# MCP960XL-L0X-RL0X_EVM_v1_teardrops.net
KiCad netlist of a schematic drawn in EAGLE
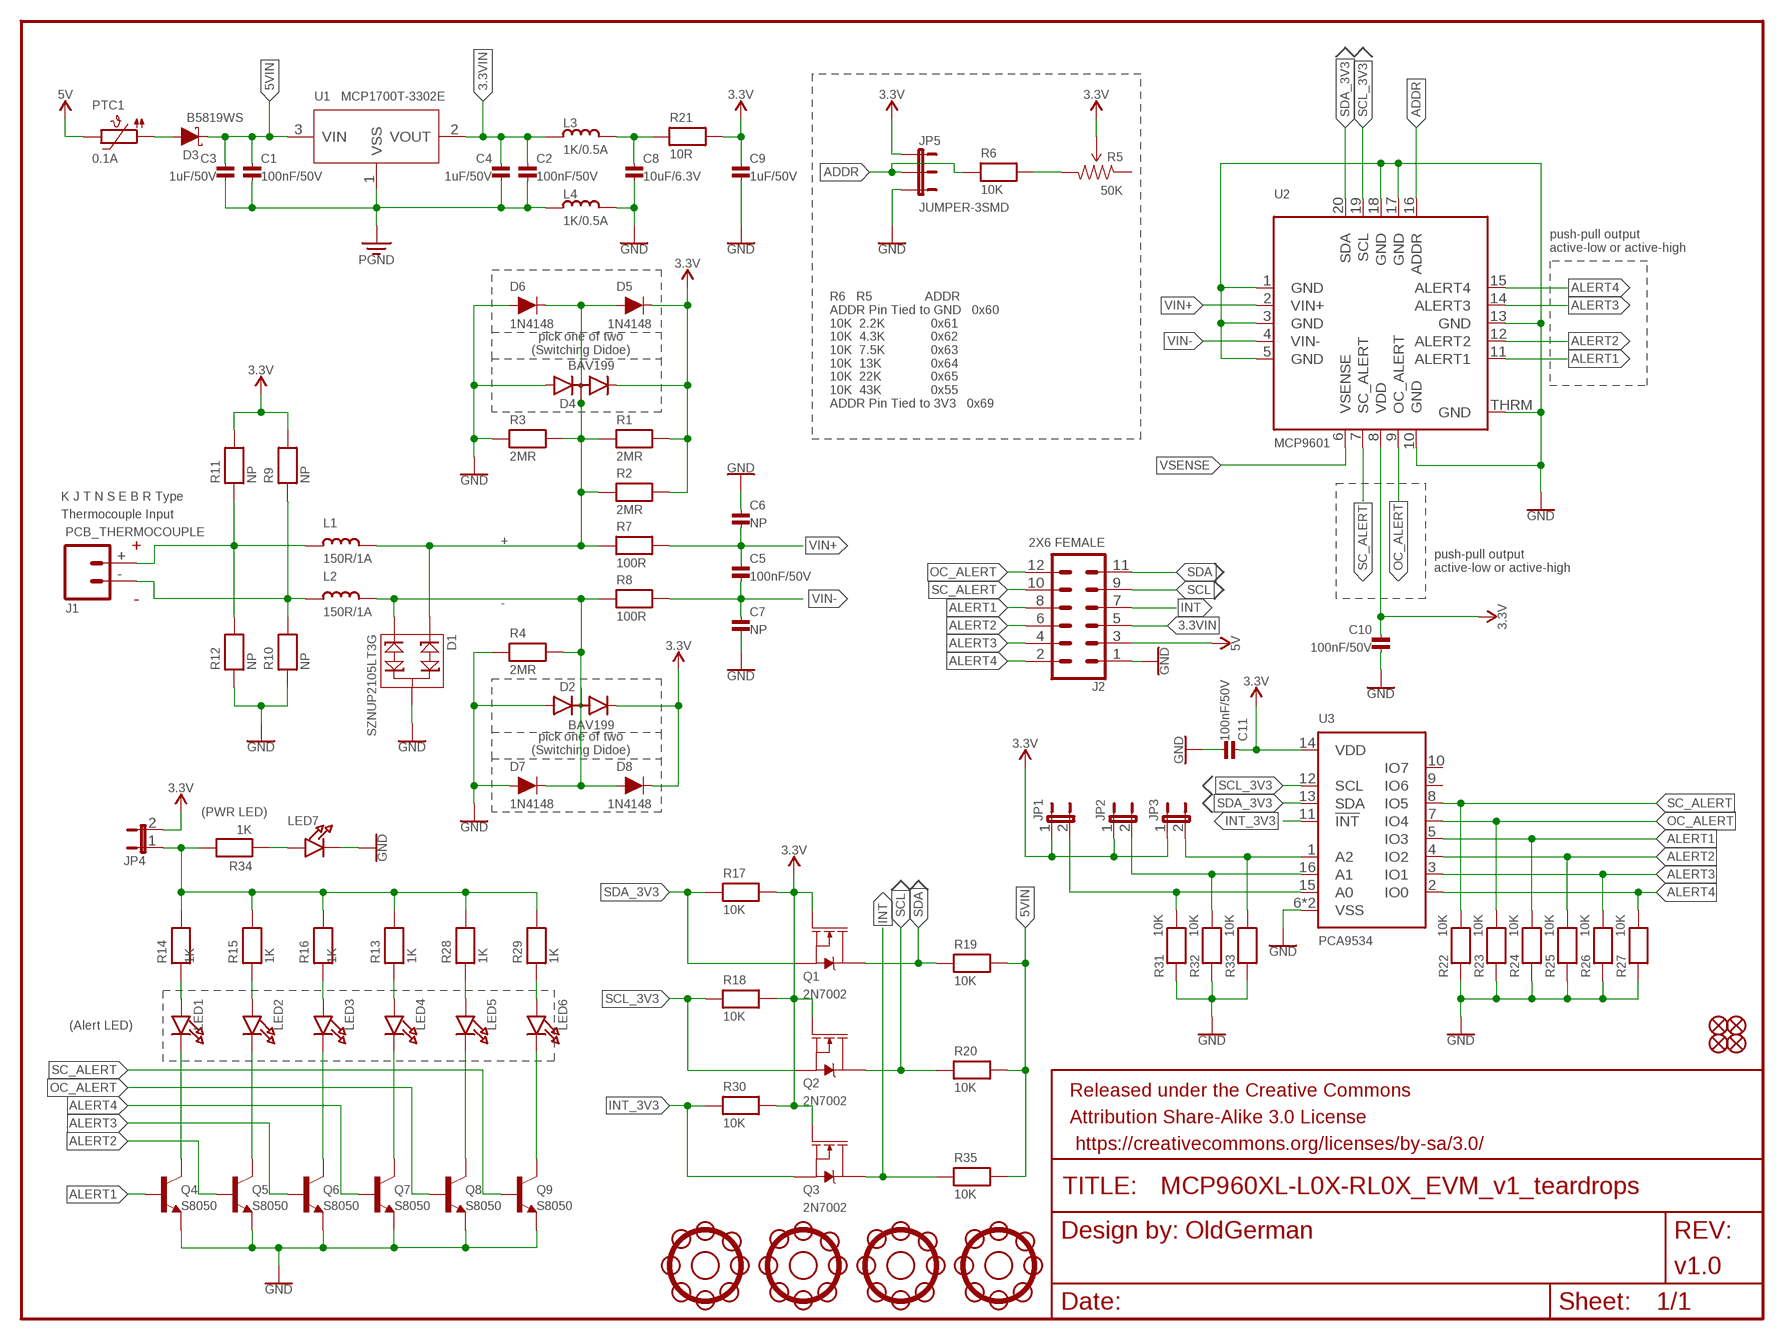
[diagram p0: schematic, sheet 1]

(export (version "E")
  (design (tool "Eeschema 10.0.6"))
  (components
    (comp (ref "C1")
      (value "100nF/50V")
      (footprint "eagle-import:0603")
      (libsource (lib "eagle-import") (part "CAP_CERAMIC0603"))
    )
    (comp (ref "C2")
      (value "100nF/50V")
      (footprint "eagle-import:0603")
      (libsource (lib "eagle-import") (part "CAP_CERAMIC0603"))
    )
    (comp (ref "C3")
      (value "1uF/50V")
      (footprint "eagle-import:0603")
      (libsource (lib "eagle-import") (part "CAP_CERAMIC0603"))
    )
    (comp (ref "C4")
      (value "1uF/50V")
      (footprint "eagle-import:0603")
      (libsource (lib "eagle-import") (part "CAP_CERAMIC0603"))
    )
    (comp (ref "C5")
      (value "100nF/50V")
      (footprint "eagle-import:0603")
      (libsource (lib "eagle-import") (part "CAP_CERAMIC0603"))
    )
    (comp (ref "C6")
      (value "NP")
      (footprint "eagle-import:0603")
      (libsource (lib "eagle-import") (part "CAP_CERAMIC0603"))
    )
    (comp (ref "C7")
      (value "NP")
      (footprint "eagle-import:0603")
      (libsource (lib "eagle-import") (part "CAP_CERAMIC0603"))
    )
    (comp (ref "C8")
      (value "10uF/6.3V")
      (footprint "eagle-import:0603")
      (libsource (lib "eagle-import") (part "CAP_CERAMIC0603"))
    )
    (comp (ref "C9")
      (value "1uF/50V")
      (footprint "eagle-import:0603")
      (libsource (lib "eagle-import") (part "CAP_CERAMIC0603"))
    )
    (comp (ref "C10")
      (value "100nF/50V")
      (footprint "eagle-import:0603")
      (libsource (lib "eagle-import") (part "CAP_CERAMIC0603"))
    )
    (comp (ref "C11")
      (value "100nF/50V")
      (footprint "eagle-import:0603")
      (libsource (lib "eagle-import") (part "CAP_CERAMIC0603"))
    )
    (comp (ref "D1")
      (value "SZNUP2105LT3G")
      (footprint "eagle-import:SOT23-3")
      (libsource (lib "eagle-import") (part "SZNUP2105LT3G"))
    )
    (comp (ref "D2")
      (value "BAV199")
      (footprint "eagle-import:SOT23-3")
      (libsource (lib "eagle-import") (part "BAV199"))
    )
    (comp (ref "D3")
      (value "B5819WS")
      (footprint "eagle-import:SOD-323")
      (libsource (lib "eagle-import") (part "DIODE_SCHOTTKYSOD323"))
    )
    (comp (ref "D4")
      (value "BAV199")
      (footprint "eagle-import:SOT23-3")
      (libsource (lib "eagle-import") (part "BAV199"))
    )
    (comp (ref "D5")
      (value "1N4148")
      (footprint "eagle-import:SOD-323")
      (libsource (lib "eagle-import") (part "DIODE"))
    )
    (comp (ref "D6")
      (value "1N4148")
      (footprint "eagle-import:SOD-323")
      (libsource (lib "eagle-import") (part "DIODE"))
    )
    (comp (ref "D7")
      (value "1N4148")
      (footprint "eagle-import:SOD-323")
      (libsource (lib "eagle-import") (part "DIODE"))
    )
    (comp (ref "D8")
      (value "1N4148")
      (footprint "eagle-import:SOD-323")
      (libsource (lib "eagle-import") (part "DIODE"))
    )
    (comp (ref "FID1")
      (value "FIDUCIAL1X2.5")
      (footprint "eagle-import:FIDUCIAL-1X2.5")
      (libsource (lib "eagle-import") (part "FIDUCIAL1X2.5"))
    )
    (comp (ref "FID2")
      (value "FIDUCIAL1X2.5")
      (footprint "eagle-import:FIDUCIAL-1X2.5")
      (libsource (lib "eagle-import") (part "FIDUCIAL1X2.5"))
    )
    (comp (ref "FID3")
      (value "FIDUCIAL1X2.5")
      (footprint "eagle-import:FIDUCIAL-1X2.5")
      (libsource (lib "eagle-import") (part "FIDUCIAL1X2.5"))
    )
    (comp (ref "FID4")
      (value "FIDUCIAL1X2.5")
      (footprint "eagle-import:FIDUCIAL-1X2.5")
      (libsource (lib "eagle-import") (part "FIDUCIAL1X2.5"))
    )
    (comp (ref "FRAME1")
      (value "FRAME-LETTER")
      (footprint "eagle-import:CREATIVE_COMMONS")
      (libsource (lib "eagle-import") (part "FRAME-LETTER"))
    )
    (comp (ref "J1")
      (value "PCB_THERMOCOUPLE")
      (footprint "eagle-import:PCC-SMP")
      (libsource (lib "eagle-import") (part "PCB_THERMOCOUPLE"))
    )
    (comp (ref "J2")
      (value "2X6 FEMALE")
      (footprint "eagle-import:2X6")
      (libsource (lib "eagle-import") (part "CONN_06X2PTH_FEMALE"))
    )
    (comp (ref "JP1")
      (value "JUMPER-2SMD-NC")
      (footprint "eagle-import:SJ_2S")
      (libsource (lib "eagle-import") (part "JUMPER-2SMD-NC"))
    )
    (comp (ref "JP2")
      (value "JUMPER-2SMD-NC")
      (footprint "eagle-import:SJ_2S")
      (libsource (lib "eagle-import") (part "JUMPER-2SMD-NC"))
    )
    (comp (ref "JP3")
      (value "JUMPER-2SMD-NC")
      (footprint "eagle-import:SJ_2S")
      (libsource (lib "eagle-import") (part "JUMPER-2SMD-NC"))
    )
    (comp (ref "JP4")
      (value "JUMPER-2SMD-NC")
      (footprint "eagle-import:SJ_2S")
      (libsource (lib "eagle-import") (part "JUMPER-2SMD-NC"))
    )
    (comp (ref "JP5")
      (value "JUMPER-3SMD")
      (footprint "eagle-import:SJ_3")
      (libsource (lib "eagle-import") (part "JUMPER-3SMD"))
    )
    (comp (ref "L1")
      (value "150R/1A")
      (footprint "eagle-import:0603")
      (libsource (lib "eagle-import") (part "INDUCTOR0603"))
    )
    (comp (ref "L2")
      (value "150R/1A")
      (footprint "eagle-import:0603")
      (libsource (lib "eagle-import") (part "INDUCTOR0603"))
    )
    (comp (ref "L3")
      (value "1K/0.5A")
      (footprint "eagle-import:0603")
      (libsource (lib "eagle-import") (part "INDUCTOR0603"))
    )
    (comp (ref "L4")
      (value "1K/0.5A")
      (footprint "eagle-import:0603")
      (libsource (lib "eagle-import") (part "INDUCTOR0603"))
    )
    (comp (ref "LED1")
      (value "LED0603")
      (footprint "eagle-import:CHIPLED_0603")
      (libsource (lib "eagle-import") (part "LED0603"))
    )
    (comp (ref "LED2")
      (value "LED0603")
      (footprint "eagle-import:CHIPLED_0603")
      (libsource (lib "eagle-import") (part "LED0603"))
    )
    (comp (ref "LED3")
      (value "LED0603")
      (footprint "eagle-import:CHIPLED_0603")
      (libsource (lib "eagle-import") (part "LED0603"))
    )
    (comp (ref "LED4")
      (value "LED0603")
      (footprint "eagle-import:CHIPLED_0603")
      (libsource (lib "eagle-import") (part "LED0603"))
    )
    (comp (ref "LED5")
      (value "LED0603")
      (footprint "eagle-import:CHIPLED_0603")
      (libsource (lib "eagle-import") (part "LED0603"))
    )
    (comp (ref "LED6")
      (value "LED0603")
      (footprint "eagle-import:CHIPLED_0603")
      (libsource (lib "eagle-import") (part "LED0603"))
    )
    (comp (ref "LED7")
      (value "LED0603")
      (footprint "eagle-import:CHIPLED_0603")
      (libsource (lib "eagle-import") (part "LED0603"))
    )
    (comp (ref "PTC1")
      (value "0.1A")
      (footprint "eagle-import:1206")
      (libsource (lib "eagle-import") (part "PTC1206"))
    )
    (comp (ref "Q1")
      (value "2N7002")
      (footprint "eagle-import:SOT23-3")
      (libsource (lib "eagle-import") (part "MOSFET-NCH-AO3404A"))
    )
    (comp (ref "Q2")
      (value "2N7002")
      (footprint "eagle-import:SOT23-3")
      (libsource (lib "eagle-import") (part "MOSFET-NCH-AO3404A"))
    )
    (comp (ref "Q3")
      (value "2N7002")
      (footprint "eagle-import:SOT23-3")
      (libsource (lib "eagle-import") (part "MOSFET-NCH-AO3404A"))
    )
    (comp (ref "Q4")
      (value "S8050")
      (footprint "eagle-import:SOT23-3")
      (libsource (lib "eagle-import") (part "TRANS_NPN-MMBT2222AL"))
    )
    (comp (ref "Q5")
      (value "S8050")
      (footprint "eagle-import:SOT23-3")
      (libsource (lib "eagle-import") (part "TRANS_NPN-MMBT2222AL"))
    )
    (comp (ref "Q6")
      (value "S8050")
      (footprint "eagle-import:SOT23-3")
      (libsource (lib "eagle-import") (part "TRANS_NPN-MMBT2222AL"))
    )
    (comp (ref "Q7")
      (value "S8050")
      (footprint "eagle-import:SOT23-3")
      (libsource (lib "eagle-import") (part "TRANS_NPN-MMBT2222AL"))
    )
    (comp (ref "Q8")
      (value "S8050")
      (footprint "eagle-import:SOT23-3")
      (libsource (lib "eagle-import") (part "TRANS_NPN-MMBT2222AL"))
    )
    (comp (ref "Q9")
      (value "S8050")
      (footprint "eagle-import:SOT23-3")
      (libsource (lib "eagle-import") (part "TRANS_NPN-MMBT2222AL"))
    )
    (comp (ref "R1")
      (value "2MR")
      (footprint "eagle-import:0603")
      (libsource (lib "eagle-import") (part "RESISTOR0603"))
    )
    (comp (ref "R2")
      (value "2MR")
      (footprint "eagle-import:0603")
      (libsource (lib "eagle-import") (part "RESISTOR0603"))
    )
    (comp (ref "R3")
      (value "2MR")
      (footprint "eagle-import:0603")
      (libsource (lib "eagle-import") (part "RESISTOR0603"))
    )
    (comp (ref "R4")
      (value "2MR")
      (footprint "eagle-import:0603")
      (libsource (lib "eagle-import") (part "RESISTOR0603"))
    )
    (comp (ref "R5")
      (value "50K")
      (footprint "eagle-import:TRIMPOT-3MM")
      (libsource (lib "eagle-import") (part "POT-SMD"))
    )
    (comp (ref "R6")
      (value "10K")
      (footprint "eagle-import:0603")
      (libsource (lib "eagle-import") (part "RESISTOR0603"))
    )
    (comp (ref "R7")
      (value "100R")
      (footprint "eagle-import:0603")
      (libsource (lib "eagle-import") (part "RESISTOR0603"))
    )
    (comp (ref "R8")
      (value "100R")
      (footprint "eagle-import:0603")
      (libsource (lib "eagle-import") (part "RESISTOR0603"))
    )
    (comp (ref "R9")
      (value "NP")
      (footprint "eagle-import:0603")
      (libsource (lib "eagle-import") (part "RESISTOR0603"))
    )
    (comp (ref "R10")
      (value "NP")
      (footprint "eagle-import:0603")
      (libsource (lib "eagle-import") (part "RESISTOR0603"))
    )
    (comp (ref "R11")
      (value "NP")
      (footprint "eagle-import:0603")
      (libsource (lib "eagle-import") (part "RESISTOR0603"))
    )
    (comp (ref "R12")
      (value "NP")
      (footprint "eagle-import:0603")
      (libsource (lib "eagle-import") (part "RESISTOR0603"))
    )
    (comp (ref "R13")
      (value "1K")
      (footprint "eagle-import:0603")
      (libsource (lib "eagle-import") (part "RESISTOR0603"))
    )
    (comp (ref "R14")
      (value "1K")
      (footprint "eagle-import:0603")
      (libsource (lib "eagle-import") (part "RESISTOR0603"))
    )
    (comp (ref "R15")
      (value "1K")
      (footprint "eagle-import:0603")
      (libsource (lib "eagle-import") (part "RESISTOR0603"))
    )
    (comp (ref "R16")
      (value "1K")
      (footprint "eagle-import:0603")
      (libsource (lib "eagle-import") (part "RESISTOR0603"))
    )
    (comp (ref "R17")
      (value "10K")
      (footprint "eagle-import:0603")
      (libsource (lib "eagle-import") (part "RESISTOR0603"))
    )
    (comp (ref "R18")
      (value "10K")
      (footprint "eagle-import:0603")
      (libsource (lib "eagle-import") (part "RESISTOR0603"))
    )
    (comp (ref "R19")
      (value "10K")
      (footprint "eagle-import:0603")
      (libsource (lib "eagle-import") (part "RESISTOR0603"))
    )
    (comp (ref "R20")
      (value "10K")
      (footprint "eagle-import:0603")
      (libsource (lib "eagle-import") (part "RESISTOR0603"))
    )
    (comp (ref "R21")
      (value "10R")
      (footprint "eagle-import:0603")
      (libsource (lib "eagle-import") (part "RESISTOR0603"))
    )
    (comp (ref "R22")
      (value "10K")
      (footprint "eagle-import:0603")
      (libsource (lib "eagle-import") (part "RESISTOR0603"))
    )
    (comp (ref "R23")
      (value "10K")
      (footprint "eagle-import:0603")
      (libsource (lib "eagle-import") (part "RESISTOR0603"))
    )
    (comp (ref "R24")
      (value "10K")
      (footprint "eagle-import:0603")
      (libsource (lib "eagle-import") (part "RESISTOR0603"))
    )
    (comp (ref "R25")
      (value "10K")
      (footprint "eagle-import:0603")
      (libsource (lib "eagle-import") (part "RESISTOR0603"))
    )
    (comp (ref "R26")
      (value "10K")
      (footprint "eagle-import:0603")
      (libsource (lib "eagle-import") (part "RESISTOR0603"))
    )
    (comp (ref "R27")
      (value "10K")
      (footprint "eagle-import:0603")
      (libsource (lib "eagle-import") (part "RESISTOR0603"))
    )
    (comp (ref "R28")
      (value "1K")
      (footprint "eagle-import:0603")
      (libsource (lib "eagle-import") (part "RESISTOR0603"))
    )
    (comp (ref "R29")
      (value "1K")
      (footprint "eagle-import:0603")
      (libsource (lib "eagle-import") (part "RESISTOR0603"))
    )
    (comp (ref "R30")
      (value "10K")
      (footprint "eagle-import:0603")
      (libsource (lib "eagle-import") (part "RESISTOR0603"))
    )
    (comp (ref "R31")
      (value "10K")
      (footprint "eagle-import:0603")
      (libsource (lib "eagle-import") (part "RESISTOR0603"))
    )
    (comp (ref "R32")
      (value "10K")
      (footprint "eagle-import:0603")
      (libsource (lib "eagle-import") (part "RESISTOR0603"))
    )
    (comp (ref "R33")
      (value "10K")
      (footprint "eagle-import:0603")
      (libsource (lib "eagle-import") (part "RESISTOR0603"))
    )
    (comp (ref "R34")
      (value "1K")
      (footprint "eagle-import:0603")
      (libsource (lib "eagle-import") (part "RESISTOR0603"))
    )
    (comp (ref "R35")
      (value "10K")
      (footprint "eagle-import:0603")
      (libsource (lib "eagle-import") (part "RESISTOR0603"))
    )
    (comp (ref "U$1")
      (value "SUN_HOLE_M3")
      (footprint "eagle-import:SUN_HOLE_M3")
      (libsource (lib "eagle-import") (part "SUN_HOLE_M3"))
    )
    (comp (ref "U$3")
      (value "SUN_HOLE_M3")
      (footprint "eagle-import:SUN_HOLE_M3")
      (libsource (lib "eagle-import") (part "SUN_HOLE_M3"))
    )
    (comp (ref "U$4")
      (value "SUN_HOLE_M3")
      (footprint "eagle-import:SUN_HOLE_M3")
      (libsource (lib "eagle-import") (part "SUN_HOLE_M3"))
    )
    (comp (ref "U$6")
      (value "SUN_HOLE_M3")
      (footprint "eagle-import:SUN_HOLE_M3")
      (libsource (lib "eagle-import") (part "SUN_HOLE_M3"))
    )
    (comp (ref "U1")
      (value "MCP1700T-3302E")
      (footprint "eagle-import:SOT23-3")
      (libsource (lib "eagle-import") (part "LDO_3PIN"))
    )
    (comp (ref "U2")
      (value "MCP9601")
      (footprint "eagle-import:VQFN20_5MM")
      (libsource (lib "eagle-import") (part "MCP9601"))
    )
    (comp (ref "U3")
      (value "PCA9534")
      (footprint "eagle-import:HVQFN16_4X4_0.65MM")
      (libsource (lib "eagle-import") (part "PCA9534"))
    )
  )
  (nets
    (net (code "1") (name "3.3V") (class "Default")
      (node (ref "C10") (pin "1") (pinfunction "P$1_1") (pintype "passive"))
      (node (ref "C11") (pin "1") (pinfunction "P$1_1") (pintype "passive"))
      (node (ref "C9") (pin "1") (pinfunction "P$1_1") (pintype "passive"))
      (node (ref "D2") (pin "3") (pinfunction "C_3") (pintype "passive"))
      (node (ref "D4") (pin "3") (pinfunction "C_3") (pintype "passive"))
      (node (ref "D5") (pin "C") (pinfunction "C_C") (pintype "passive"))
      (node (ref "D8") (pin "C") (pinfunction "C_C") (pintype "passive"))
      (node (ref "JP1") (pin "1") (pinfunction "1_1") (pintype "passive"))
      (node (ref "JP2") (pin "1") (pinfunction "1_1") (pintype "passive"))
      (node (ref "JP3") (pin "1") (pinfunction "1_1") (pintype "passive"))
      (node (ref "JP4") (pin "2") (pinfunction "2_2") (pintype "passive"))
      (node (ref "JP5") (pin "1") (pinfunction "1_1") (pintype "passive"))
      (node (ref "Q1") (pin "1") (pinfunction "G_1") (pintype "bidirectional"))
      (node (ref "Q2") (pin "1") (pinfunction "G_1") (pintype "bidirectional"))
      (node (ref "Q3") (pin "1") (pinfunction "G_1") (pintype "bidirectional"))
      (node (ref "R1") (pin "2") (pinfunction "2_2") (pintype "passive"))
      (node (ref "R11") (pin "2") (pinfunction "2_2") (pintype "passive"))
      (node (ref "R17") (pin "2") (pinfunction "2_2") (pintype "passive"))
      (node (ref "R18") (pin "2") (pinfunction "2_2") (pintype "passive"))
      (node (ref "R2") (pin "2") (pinfunction "2_2") (pintype "passive"))
      (node (ref "R21") (pin "2") (pinfunction "2_2") (pintype "passive"))
      (node (ref "R30") (pin "2") (pinfunction "2_2") (pintype "passive"))
      (node (ref "R5") (pin "2") (pinfunction "WIPER_2") (pintype "passive"))
      (node (ref "R9") (pin "2") (pinfunction "2_2") (pintype "passive"))
      (node (ref "U2") (pin "8") (pinfunction "VDD_8") (pintype "bidirectional"))
      (node (ref "U3") (pin "14") (pinfunction "VDD_14") (pintype "power_in"))
    )
    (net (code "2") (name "3.3VIN") (class "Default")
      (node (ref "C2") (pin "1") (pinfunction "P$1_1") (pintype "passive"))
      (node (ref "C4") (pin "1") (pinfunction "P$1_1") (pintype "passive"))
      (node (ref "J2") (pin "5") (pinfunction "5_5") (pintype "passive"))
      (node (ref "L3") (pin "1") (pinfunction "1_1") (pintype "passive"))
      (node (ref "U1") (pin "2") (pinfunction "VOUT_2") (pintype "bidirectional"))
    )
    (net (code "3") (name "5V") (class "Default")
      (node (ref "J2") (pin "3") (pinfunction "3_3") (pintype "passive"))
      (node (ref "PTC1") (pin "2") (pinfunction "2_2") (pintype "passive"))
    )
    (net (code "4") (name "5VIN") (class "Default")
      (node (ref "C1") (pin "1") (pinfunction "P$1_1") (pintype "passive"))
      (node (ref "C3") (pin "1") (pinfunction "P$1_1") (pintype "passive"))
      (node (ref "D3") (pin "C") (pinfunction "C_C") (pintype "passive"))
      (node (ref "R19") (pin "2") (pinfunction "2_2") (pintype "passive"))
      (node (ref "R20") (pin "2") (pinfunction "2_2") (pintype "passive"))
      (node (ref "R35") (pin "2") (pinfunction "2_2") (pintype "passive"))
      (node (ref "U1") (pin "3") (pinfunction "VIN_3") (pintype "bidirectional"))
    )
    (net (code "5") (name "ADDR") (class "Default")
      (node (ref "JP5") (pin "2") (pinfunction "2_2") (pintype "passive"))
      (node (ref "R6") (pin "1") (pinfunction "1_1") (pintype "passive"))
      (node (ref "U2") (pin "16") (pinfunction "ADDR_16") (pintype "bidirectional"))
    )
    (net (code "6") (name "ALERT1") (class "Default")
      (node (ref "J2") (pin "8") (pinfunction "8_8") (pintype "passive"))
      (node (ref "Q4") (pin "1") (pinfunction "B_1") (pintype "passive"))
      (node (ref "R24") (pin "2") (pinfunction "2_2") (pintype "passive"))
      (node (ref "U2") (pin "11") (pinfunction "ALERT1_11") (pintype "bidirectional"))
      (node (ref "U3") (pin "5") (pinfunction "IO3_5") (pintype "bidirectional"))
    )
    (net (code "7") (name "ALERT2") (class "Default")
      (node (ref "J2") (pin "6") (pinfunction "6_6") (pintype "passive"))
      (node (ref "Q5") (pin "1") (pinfunction "B_1") (pintype "passive"))
      (node (ref "R25") (pin "2") (pinfunction "2_2") (pintype "passive"))
      (node (ref "U2") (pin "12") (pinfunction "ALERT2_12") (pintype "bidirectional"))
      (node (ref "U3") (pin "4") (pinfunction "IO2_4") (pintype "bidirectional"))
    )
    (net (code "8") (name "ALERT3") (class "Default")
      (node (ref "J2") (pin "4") (pinfunction "4_4") (pintype "passive"))
      (node (ref "Q6") (pin "1") (pinfunction "B_1") (pintype "passive"))
      (node (ref "R26") (pin "2") (pinfunction "2_2") (pintype "passive"))
      (node (ref "U2") (pin "14") (pinfunction "ALERT3_14") (pintype "bidirectional"))
      (node (ref "U3") (pin "3") (pinfunction "IO1_3") (pintype "bidirectional"))
    )
    (net (code "9") (name "ALERT4") (class "Default")
      (node (ref "J2") (pin "2") (pinfunction "2_2") (pintype "passive"))
      (node (ref "Q7") (pin "1") (pinfunction "B_1") (pintype "passive"))
      (node (ref "R27") (pin "2") (pinfunction "2_2") (pintype "passive"))
      (node (ref "U2") (pin "15") (pinfunction "ALERT4_15") (pintype "bidirectional"))
      (node (ref "U3") (pin "2") (pinfunction "IO0_2") (pintype "bidirectional"))
    )
    (net (code "10") (name "GND") (class "Default")
      (node (ref "C10") (pin "2") (pinfunction "P$2_2") (pintype "passive"))
      (node (ref "C11") (pin "2") (pinfunction "P$2_2") (pintype "passive"))
      (node (ref "C6") (pin "1") (pinfunction "P$1_1") (pintype "passive"))
      (node (ref "C7") (pin "2") (pinfunction "P$2_2") (pintype "passive"))
      (node (ref "C8") (pin "2") (pinfunction "P$2_2") (pintype "passive"))
      (node (ref "C9") (pin "2") (pinfunction "P$2_2") (pintype "passive"))
      (node (ref "D1") (pin "3") (pinfunction "3_3") (pintype "bidirectional"))
      (node (ref "D2") (pin "1") (pinfunction "A_1") (pintype "passive"))
      (node (ref "D4") (pin "1") (pinfunction "A_1") (pintype "passive"))
      (node (ref "D6") (pin "A") (pinfunction "A_A") (pintype "passive"))
      (node (ref "D7") (pin "A") (pinfunction "A_A") (pintype "passive"))
      (node (ref "J2") (pin "1") (pinfunction "1_1") (pintype "passive"))
      (node (ref "JP5") (pin "3") (pinfunction "3_3") (pintype "passive"))
      (node (ref "L4") (pin "2") (pinfunction "2_2") (pintype "passive"))
      (node (ref "LED7") (pin "C") (pinfunction "C_C") (pintype "passive"))
      (node (ref "Q4") (pin "2") (pinfunction "E_2") (pintype "passive"))
      (node (ref "Q5") (pin "2") (pinfunction "E_2") (pintype "passive"))
      (node (ref "Q6") (pin "2") (pinfunction "E_2") (pintype "passive"))
      (node (ref "Q7") (pin "2") (pinfunction "E_2") (pintype "passive"))
      (node (ref "Q8") (pin "2") (pinfunction "E_2") (pintype "passive"))
      (node (ref "Q9") (pin "2") (pinfunction "E_2") (pintype "passive"))
      (node (ref "R10") (pin "1") (pinfunction "1_1") (pintype "passive"))
      (node (ref "R12") (pin "1") (pinfunction "1_1") (pintype "passive"))
      (node (ref "R22") (pin "1") (pinfunction "1_1") (pintype "passive"))
      (node (ref "R23") (pin "1") (pinfunction "1_1") (pintype "passive"))
      (node (ref "R24") (pin "1") (pinfunction "1_1") (pintype "passive"))
      (node (ref "R25") (pin "1") (pinfunction "1_1") (pintype "passive"))
      (node (ref "R26") (pin "1") (pinfunction "1_1") (pintype "passive"))
      (node (ref "R27") (pin "1") (pinfunction "1_1") (pintype "passive"))
      (node (ref "R3") (pin "1") (pinfunction "1_1") (pintype "passive"))
      (node (ref "R31") (pin "1") (pinfunction "1_1") (pintype "passive"))
      (node (ref "R32") (pin "1") (pinfunction "1_1") (pintype "passive"))
      (node (ref "R33") (pin "1") (pinfunction "1_1") (pintype "passive"))
      (node (ref "R4") (pin "1") (pinfunction "1_1") (pintype "passive"))
      (node (ref "U2") (pin "1") (pinfunction "GND_1") (pintype "bidirectional"))
      (node (ref "U2") (pin "10") (pinfunction "GND_10") (pintype "bidirectional"))
      (node (ref "U2") (pin "13") (pinfunction "GND_13") (pintype "bidirectional"))
      (node (ref "U2") (pin "17") (pinfunction "GND_17") (pintype "bidirectional"))
      (node (ref "U2") (pin "18") (pinfunction "GND_18") (pintype "bidirectional"))
      (node (ref "U2") (pin "3") (pinfunction "GND_3") (pintype "bidirectional"))
      (node (ref "U2") (pin "5") (pinfunction "GND_5") (pintype "bidirectional"))
      (node (ref "U2") (pin "THRM") (pinfunction "GND_THRM") (pintype "bidirectional"))
      (node (ref "U3") (pin "6") (pinfunction "VSS_6") (pintype "power_in"))
      (node (ref "U3") (pin "PAD") (pinfunction "VSS_PAD") (pintype "power_in"))
    )
    (net (code "11") (name "INT") (class "Default")
      (node (ref "J2") (pin "7") (pinfunction "7_7") (pintype "passive"))
      (node (ref "Q3") (pin "3") (pinfunction "D_3") (pintype "bidirectional"))
      (node (ref "R35") (pin "1") (pinfunction "1_1") (pintype "passive"))
    )
    (net (code "12") (name "INT_3V3") (class "Default")
      (node (ref "Q3") (pin "2") (pinfunction "S_2") (pintype "bidirectional"))
      (node (ref "R30") (pin "1") (pinfunction "1_1") (pintype "passive"))
      (node (ref "U3") (pin "11") (pinfunction "~{INT}_11") (pintype "open_collector"))
    )
    (net (code "13") (name "Net-(C8-P$1)") (class "Default")
      (node (ref "C8") (pin "1") (pinfunction "P$1_1") (pintype "passive"))
      (node (ref "L3") (pin "2") (pinfunction "2_2") (pintype "passive"))
      (node (ref "R21") (pin "1") (pinfunction "1_1") (pintype "passive"))
    )
    (net (code "14") (name "Net-(D2-AC)") (class "Default")
      (node (ref "D1") (pin "2") (pinfunction "2_2") (pintype "power_in"))
      (node (ref "D2") (pin "2") (pinfunction "AC_2") (pintype "passive"))
      (node (ref "D7") (pin "C") (pinfunction "C_C") (pintype "passive"))
      (node (ref "D8") (pin "A") (pinfunction "A_A") (pintype "passive"))
      (node (ref "L2") (pin "2") (pinfunction "2_2") (pintype "passive"))
      (node (ref "R4") (pin "2") (pinfunction "2_2") (pintype "passive"))
      (node (ref "R8") (pin "1") (pinfunction "1_1") (pintype "passive"))
    )
    (net (code "15") (name "Net-(D3-PadA)") (class "Default")
      (node (ref "D3") (pin "A") (pinfunction "A_A") (pintype "passive"))
      (node (ref "PTC1") (pin "1") (pinfunction "1_1") (pintype "passive"))
    )
    (net (code "16") (name "Net-(D4-AC)") (class "Default")
      (node (ref "D1") (pin "1") (pinfunction "1_1") (pintype "power_in"))
      (node (ref "D4") (pin "2") (pinfunction "AC_2") (pintype "passive"))
      (node (ref "D5") (pin "A") (pinfunction "A_A") (pintype "passive"))
      (node (ref "D6") (pin "C") (pinfunction "C_C") (pintype "passive"))
      (node (ref "L1") (pin "2") (pinfunction "2_2") (pintype "passive"))
      (node (ref "R1") (pin "1") (pinfunction "1_1") (pintype "passive"))
      (node (ref "R2") (pin "1") (pinfunction "1_1") (pintype "passive"))
      (node (ref "R3") (pin "2") (pinfunction "2_2") (pintype "passive"))
      (node (ref "R7") (pin "1") (pinfunction "1_1") (pintype "passive"))
    )
    (net (code "17") (name "Net-(J1-Pad+)") (class "Default")
      (node (ref "J1") (pin "+") (pinfunction "+_+") (pintype "passive"))
      (node (ref "L1") (pin "1") (pinfunction "1_1") (pintype "passive"))
      (node (ref "R11") (pin "1") (pinfunction "1_1") (pintype "passive"))
      (node (ref "R12") (pin "2") (pinfunction "2_2") (pintype "passive"))
    )
    (net (code "18") (name "Net-(J1-Pad-)") (class "Default")
      (node (ref "J1") (pin "-") (pinfunction "-_-") (pintype "passive"))
      (node (ref "L2") (pin "1") (pinfunction "1_1") (pintype "passive"))
      (node (ref "R10") (pin "2") (pinfunction "2_2") (pintype "passive"))
      (node (ref "R9") (pin "1") (pinfunction "1_1") (pintype "passive"))
    )
    (net (code "19") (name "Net-(JP4-Pad1)") (class "Default")
      (node (ref "JP4") (pin "1") (pinfunction "1_1") (pintype "passive"))
      (node (ref "R13") (pin "2") (pinfunction "2_2") (pintype "passive"))
      (node (ref "R14") (pin "2") (pinfunction "2_2") (pintype "passive"))
      (node (ref "R15") (pin "2") (pinfunction "2_2") (pintype "passive"))
      (node (ref "R16") (pin "2") (pinfunction "2_2") (pintype "passive"))
      (node (ref "R28") (pin "2") (pinfunction "2_2") (pintype "passive"))
      (node (ref "R29") (pin "2") (pinfunction "2_2") (pintype "passive"))
      (node (ref "R34") (pin "2") (pinfunction "2_2") (pintype "passive"))
    )
    (net (code "20") (name "Net-(LED1-PadA)") (class "Default")
      (node (ref "LED1") (pin "A") (pinfunction "A_A") (pintype "passive"))
      (node (ref "R14") (pin "1") (pinfunction "1_1") (pintype "passive"))
    )
    (net (code "21") (name "Net-(LED2-PadA)") (class "Default")
      (node (ref "LED2") (pin "A") (pinfunction "A_A") (pintype "passive"))
      (node (ref "R15") (pin "1") (pinfunction "1_1") (pintype "passive"))
    )
    (net (code "22") (name "Net-(LED3-PadA)") (class "Default")
      (node (ref "LED3") (pin "A") (pinfunction "A_A") (pintype "passive"))
      (node (ref "R16") (pin "1") (pinfunction "1_1") (pintype "passive"))
    )
    (net (code "23") (name "Net-(LED4-PadA)") (class "Default")
      (node (ref "LED4") (pin "A") (pinfunction "A_A") (pintype "passive"))
      (node (ref "R13") (pin "1") (pinfunction "1_1") (pintype "passive"))
    )
    (net (code "24") (name "Net-(LED5-PadA)") (class "Default")
      (node (ref "LED5") (pin "A") (pinfunction "A_A") (pintype "passive"))
      (node (ref "R28") (pin "1") (pinfunction "1_1") (pintype "passive"))
    )
    (net (code "25") (name "Net-(LED6-PadA)") (class "Default")
      (node (ref "LED6") (pin "A") (pinfunction "A_A") (pintype "passive"))
      (node (ref "R29") (pin "1") (pinfunction "1_1") (pintype "passive"))
    )
    (net (code "26") (name "Net-(LED7-PadA)") (class "Default")
      (node (ref "LED7") (pin "A") (pinfunction "A_A") (pintype "passive"))
      (node (ref "R34") (pin "1") (pinfunction "1_1") (pintype "passive"))
    )
    (net (code "27") (name "Net-(Q4-C)") (class "Default")
      (node (ref "LED1") (pin "C") (pinfunction "C_C") (pintype "passive"))
      (node (ref "Q4") (pin "3") (pinfunction "C_3") (pintype "passive"))
    )
    (net (code "28") (name "Net-(Q5-C)") (class "Default")
      (node (ref "LED2") (pin "C") (pinfunction "C_C") (pintype "passive"))
      (node (ref "Q5") (pin "3") (pinfunction "C_3") (pintype "passive"))
    )
    (net (code "29") (name "Net-(Q6-C)") (class "Default")
      (node (ref "LED3") (pin "C") (pinfunction "C_C") (pintype "passive"))
      (node (ref "Q6") (pin "3") (pinfunction "C_3") (pintype "passive"))
    )
    (net (code "30") (name "Net-(Q7-C)") (class "Default")
      (node (ref "LED4") (pin "C") (pinfunction "C_C") (pintype "passive"))
      (node (ref "Q7") (pin "3") (pinfunction "C_3") (pintype "passive"))
    )
    (net (code "31") (name "Net-(Q8-C)") (class "Default")
      (node (ref "LED5") (pin "C") (pinfunction "C_C") (pintype "passive"))
      (node (ref "Q8") (pin "3") (pinfunction "C_3") (pintype "passive"))
    )
    (net (code "32") (name "Net-(Q9-C)") (class "Default")
      (node (ref "LED6") (pin "C") (pinfunction "C_C") (pintype "passive"))
      (node (ref "Q9") (pin "3") (pinfunction "C_3") (pintype "passive"))
    )
    (net (code "33") (name "Net-(R5-CW)") (class "Default")
      (node (ref "R5") (pin "1") (pinfunction "CW_1") (pintype "passive"))
      (node (ref "R6") (pin "2") (pinfunction "2_2") (pintype "passive"))
    )
    (net (code "34") (name "Net-(U3-A0)") (class "Default")
      (node (ref "JP1") (pin "2") (pinfunction "2_2") (pintype "passive"))
      (node (ref "R31") (pin "2") (pinfunction "2_2") (pintype "passive"))
      (node (ref "U3") (pin "15") (pinfunction "A0_15") (pintype "input"))
    )
    (net (code "35") (name "Net-(U3-A1)") (class "Default")
      (node (ref "JP2") (pin "2") (pinfunction "2_2") (pintype "passive"))
      (node (ref "R32") (pin "2") (pinfunction "2_2") (pintype "passive"))
      (node (ref "U3") (pin "16") (pinfunction "A1_16") (pintype "input"))
    )
    (net (code "36") (name "Net-(U3-A2)") (class "Default")
      (node (ref "JP3") (pin "2") (pinfunction "2_2") (pintype "passive"))
      (node (ref "R33") (pin "2") (pinfunction "2_2") (pintype "passive"))
      (node (ref "U3") (pin "1") (pinfunction "A2_1") (pintype "input"))
    )
    (net (code "37") (name "OC_ALERT") (class "Default")
      (node (ref "J2") (pin "12") (pinfunction "12_12") (pintype "passive"))
      (node (ref "Q8") (pin "1") (pinfunction "B_1") (pintype "passive"))
      (node (ref "R23") (pin "2") (pinfunction "2_2") (pintype "passive"))
      (node (ref "U2") (pin "9") (pinfunction "OC_ALERT_9") (pintype "bidirectional"))
      (node (ref "U3") (pin "7") (pinfunction "IO4_7") (pintype "bidirectional"))
    )
    (net (code "38") (name "PGND") (class "Default")
      (node (ref "C1") (pin "2") (pinfunction "P$2_2") (pintype "passive"))
      (node (ref "C2") (pin "2") (pinfunction "P$2_2") (pintype "passive"))
      (node (ref "C3") (pin "2") (pinfunction "P$2_2") (pintype "passive"))
      (node (ref "C4") (pin "2") (pinfunction "P$2_2") (pintype "passive"))
      (node (ref "L4") (pin "1") (pinfunction "1_1") (pintype "passive"))
      (node (ref "U1") (pin "1") (pinfunction "VSS_1") (pintype "bidirectional"))
    )
    (net (code "39") (name "SCL") (class "Default")
      (node (ref "J2") (pin "9") (pinfunction "9_9") (pintype "passive"))
      (node (ref "Q2") (pin "3") (pinfunction "D_3") (pintype "bidirectional"))
      (node (ref "R20") (pin "1") (pinfunction "1_1") (pintype "passive"))
    )
    (net (code "40") (name "SCL_3V3") (class "Default")
      (node (ref "Q2") (pin "2") (pinfunction "S_2") (pintype "bidirectional"))
      (node (ref "R18") (pin "1") (pinfunction "1_1") (pintype "passive"))
      (node (ref "U2") (pin "19") (pinfunction "SCL_19") (pintype "bidirectional"))
      (node (ref "U3") (pin "12") (pinfunction "SCL_12") (pintype "input"))
    )
    (net (code "41") (name "SC_ALERT") (class "Default")
      (node (ref "J2") (pin "10") (pinfunction "10_10") (pintype "passive"))
      (node (ref "Q9") (pin "1") (pinfunction "B_1") (pintype "passive"))
      (node (ref "R22") (pin "2") (pinfunction "2_2") (pintype "passive"))
      (node (ref "U2") (pin "7") (pinfunction "SC_ALERT_7") (pintype "bidirectional"))
      (node (ref "U3") (pin "8") (pinfunction "IO5_8") (pintype "bidirectional"))
    )
    (net (code "42") (name "SDA") (class "Default")
      (node (ref "J2") (pin "11") (pinfunction "11_11") (pintype "passive"))
      (node (ref "Q1") (pin "3") (pinfunction "D_3") (pintype "bidirectional"))
      (node (ref "R19") (pin "1") (pinfunction "1_1") (pintype "passive"))
    )
    (net (code "43") (name "SDA_3V3") (class "Default")
      (node (ref "Q1") (pin "2") (pinfunction "S_2") (pintype "bidirectional"))
      (node (ref "R17") (pin "1") (pinfunction "1_1") (pintype "passive"))
      (node (ref "U2") (pin "20") (pinfunction "SDA_20") (pintype "bidirectional"))
      (node (ref "U3") (pin "13") (pinfunction "SDA_13") (pintype "bidirectional"))
    )
    (net (code "44") (name "VIN+") (class "Default")
      (node (ref "C5") (pin "1") (pinfunction "P$1_1") (pintype "passive"))
      (node (ref "C6") (pin "2") (pinfunction "P$2_2") (pintype "passive"))
      (node (ref "R7") (pin "2") (pinfunction "2_2") (pintype "passive"))
      (node (ref "U2") (pin "2") (pinfunction "VIN+_2") (pintype "bidirectional"))
    )
    (net (code "45") (name "VIN-") (class "Default")
      (node (ref "C5") (pin "2") (pinfunction "P$2_2") (pintype "passive"))
      (node (ref "C7") (pin "1") (pinfunction "P$1_1") (pintype "passive"))
      (node (ref "R8") (pin "2") (pinfunction "2_2") (pintype "passive"))
      (node (ref "U2") (pin "4") (pinfunction "VIN-_4") (pintype "bidirectional"))
    )
    (net (code "46") (name "VSENSE") (class "Default")
      (node (ref "U2") (pin "6") (pinfunction "VSENSE_6") (pintype "bidirectional"))
    )
    (net (code "47") (name "unconnected-(R5-CCW-Pad3)") (class "Default")
      (node (ref "R5") (pin "3") (pinfunction "CCW_3") (pintype "passive"))
    )
    (net (code "48") (name "unconnected-(U3-IO6-Pad9)") (class "Default")
      (node (ref "U3") (pin "9") (pinfunction "IO6_9") (pintype "bidirectional"))
    )
    (net (code "49") (name "unconnected-(U3-IO7-Pad10)") (class "Default")
      (node (ref "U3") (pin "10") (pinfunction "IO7_10") (pintype "bidirectional"))
    )
  )
)
